# Analog_Frontend_OpAmp.net
KiCad netlist of a schematic drawn in Altium Designer
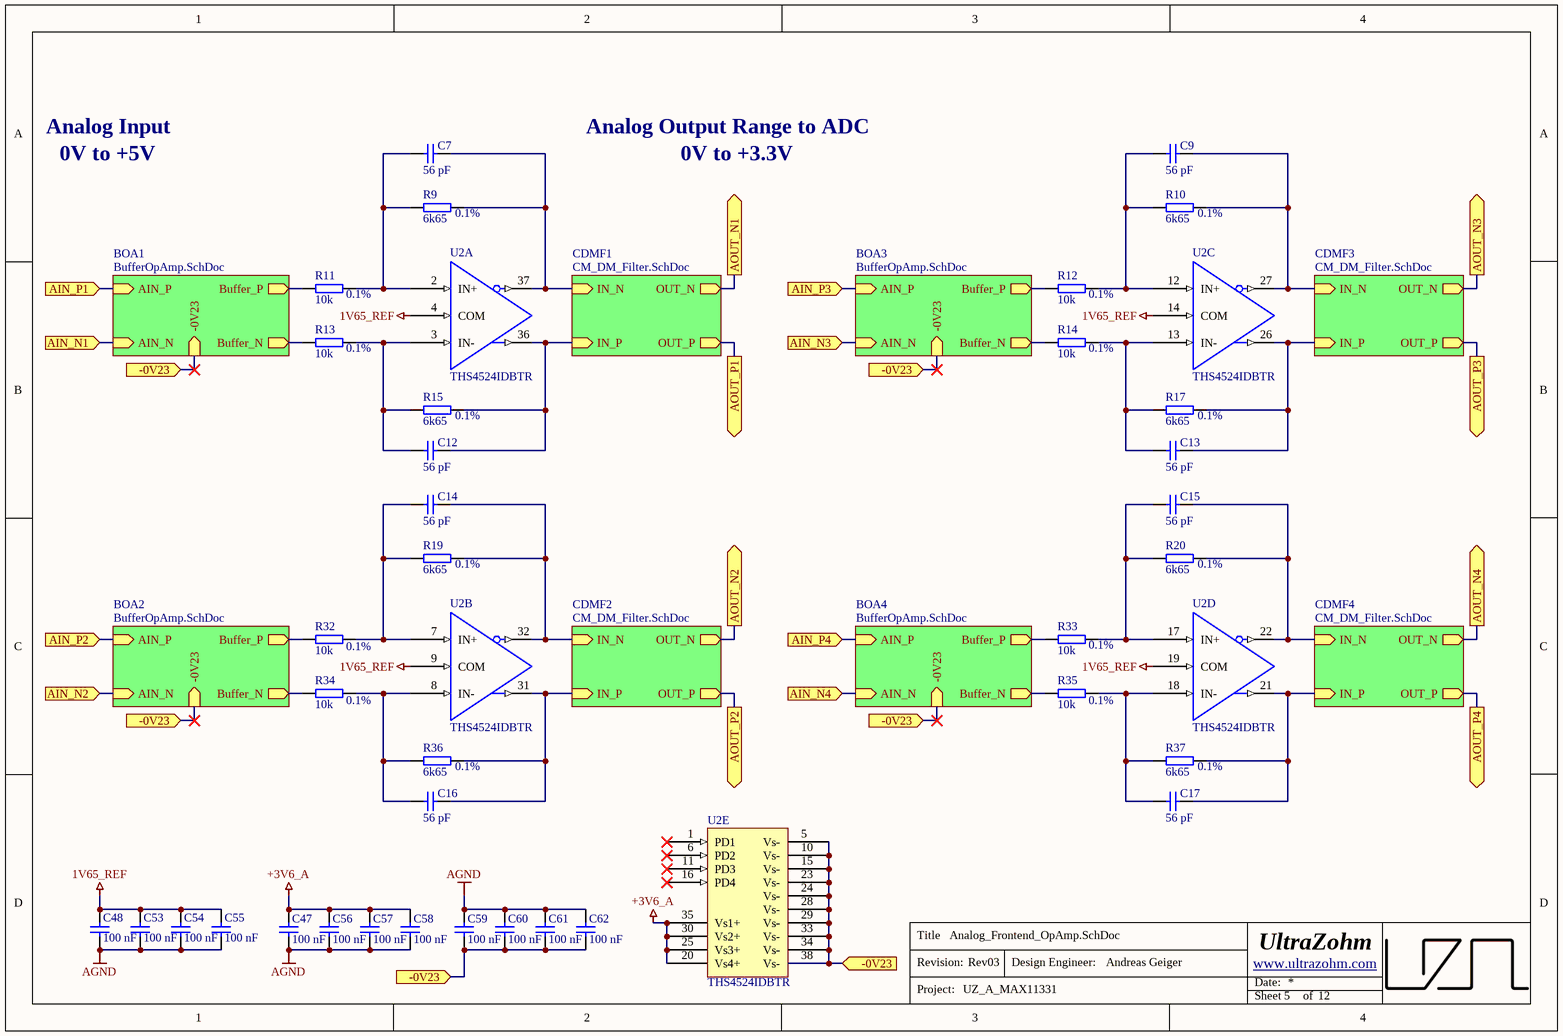
[diagram p0: Analog_Frontend_OpAmp.SchDoc]

(export (version "E")
  (design (tool "Eeschema 10.0.6"))
  (components
    (comp (ref "C7")
      (value "56 pF")
      (footprint "C_0402_TE")
      (description "Generic capacitor")
      (fields
        (field (name "MANUFACTURER PART NUMBER") "UZgen_C_0402_56pF_50V_NP0")
        (field (name "MANUFACTURER") "UZgen")
        (field (name "CREATED FROM") "UZgenTool")
      )
      (libsource (lib "user") (part "CAP-NP"))
    )
    (comp (ref "C9")
      (value "56 pF")
      (footprint "C_0402_TE")
      (description "Generic capacitor")
      (fields
        (field (name "MANUFACTURER PART NUMBER") "UZgen_C_0402_56pF_50V_NP0")
        (field (name "MANUFACTURER") "UZgen")
        (field (name "CREATED FROM") "UZgenTool")
      )
      (libsource (lib "user") (part "CAP-NP"))
    )
    (comp (ref "C12")
      (value "56 pF")
      (footprint "C_0402_TE")
      (description "Generic capacitor")
      (fields
        (field (name "MANUFACTURER PART NUMBER") "UZgen_C_0402_56pF_50V_NP0")
        (field (name "MANUFACTURER") "UZgen")
        (field (name "CREATED FROM") "UZgenTool")
      )
      (libsource (lib "user") (part "CAP-NP"))
    )
    (comp (ref "C13")
      (value "56 pF")
      (footprint "C_0402_TE")
      (description "Generic capacitor")
      (fields
        (field (name "MANUFACTURER PART NUMBER") "UZgen_C_0402_56pF_50V_NP0")
        (field (name "MANUFACTURER") "UZgen")
        (field (name "CREATED FROM") "UZgenTool")
      )
      (libsource (lib "user") (part "CAP-NP"))
    )
    (comp (ref "C14")
      (value "56 pF")
      (footprint "C_0402_TE")
      (description "Generic capacitor")
      (fields
        (field (name "MANUFACTURER PART NUMBER") "UZgen_C_0402_56pF_50V_NP0")
        (field (name "MANUFACTURER") "UZgen")
        (field (name "CREATED FROM") "UZgenTool")
      )
      (libsource (lib "user") (part "CAP-NP"))
    )
    (comp (ref "C15")
      (value "56 pF")
      (footprint "C_0402_TE")
      (description "Generic capacitor")
      (fields
        (field (name "MANUFACTURER PART NUMBER") "UZgen_C_0402_56pF_50V_NP0")
        (field (name "MANUFACTURER") "UZgen")
        (field (name "CREATED FROM") "UZgenTool")
      )
      (libsource (lib "user") (part "CAP-NP"))
    )
    (comp (ref "C16")
      (value "56 pF")
      (footprint "C_0402_TE")
      (description "Generic capacitor")
      (fields
        (field (name "MANUFACTURER PART NUMBER") "UZgen_C_0402_56pF_50V_NP0")
        (field (name "MANUFACTURER") "UZgen")
        (field (name "CREATED FROM") "UZgenTool")
      )
      (libsource (lib "user") (part "CAP-NP"))
    )
    (comp (ref "C17")
      (value "56 pF")
      (footprint "C_0402_TE")
      (description "Generic capacitor")
      (fields
        (field (name "MANUFACTURER PART NUMBER") "UZgen_C_0402_56pF_50V_NP0")
        (field (name "MANUFACTURER") "UZgen")
        (field (name "CREATED FROM") "UZgenTool")
      )
      (libsource (lib "user") (part "CAP-NP"))
    )
    (comp (ref "C47")
      (value "100 nF")
      (footprint "C_0402_TE")
      (description "Generic capacitor")
      (fields
        (field (name "MANUFACTURER PART NUMBER") "UZgen_C_0402_100nF_50V_X7R")
        (field (name "MANUFACTURER") "UZgen")
        (field (name "CREATED FROM") "UZgenTool")
      )
      (libsource (lib "user") (part "CAP-NP"))
    )
    (comp (ref "C48")
      (value "100 nF")
      (footprint "C_0402_TE")
      (description "Generic capacitor")
      (fields
        (field (name "MANUFACTURER PART NUMBER") "UZgen_C_0402_100nF_50V_X7R")
        (field (name "MANUFACTURER") "UZgen")
        (field (name "CREATED FROM") "UZgenTool")
      )
      (libsource (lib "user") (part "CAP-NP"))
    )
    (comp (ref "C53")
      (value "100 nF")
      (footprint "C_0402_TE")
      (description "Generic capacitor")
      (fields
        (field (name "MANUFACTURER PART NUMBER") "UZgen_C_0402_100nF_50V_X7R")
        (field (name "MANUFACTURER") "UZgen")
        (field (name "CREATED FROM") "UZgenTool")
      )
      (libsource (lib "user") (part "CAP-NP"))
    )
    (comp (ref "C54")
      (value "100 nF")
      (footprint "C_0402_TE")
      (description "Generic capacitor")
      (fields
        (field (name "MANUFACTURER PART NUMBER") "UZgen_C_0402_100nF_50V_X7R")
        (field (name "MANUFACTURER") "UZgen")
        (field (name "CREATED FROM") "UZgenTool")
      )
      (libsource (lib "user") (part "CAP-NP"))
    )
    (comp (ref "C55")
      (value "100 nF")
      (footprint "C_0402_TE")
      (description "Generic capacitor")
      (fields
        (field (name "MANUFACTURER PART NUMBER") "UZgen_C_0402_100nF_50V_X7R")
        (field (name "MANUFACTURER") "UZgen")
        (field (name "CREATED FROM") "UZgenTool")
      )
      (libsource (lib "user") (part "CAP-NP"))
    )
    (comp (ref "C56")
      (value "100 nF")
      (footprint "C_0402_TE")
      (description "Generic capacitor")
      (fields
        (field (name "MANUFACTURER PART NUMBER") "UZgen_C_0402_100nF_50V_X7R")
        (field (name "MANUFACTURER") "UZgen")
        (field (name "CREATED FROM") "UZgenTool")
      )
      (libsource (lib "user") (part "CAP-NP"))
    )
    (comp (ref "C57")
      (value "100 nF")
      (footprint "C_0402_TE")
      (description "Generic capacitor")
      (fields
        (field (name "MANUFACTURER PART NUMBER") "UZgen_C_0402_100nF_50V_X7R")
        (field (name "MANUFACTURER") "UZgen")
        (field (name "CREATED FROM") "UZgenTool")
      )
      (libsource (lib "user") (part "CAP-NP"))
    )
    (comp (ref "C58")
      (value "100 nF")
      (footprint "C_0402_TE")
      (description "Generic capacitor")
      (fields
        (field (name "MANUFACTURER PART NUMBER") "UZgen_C_0402_100nF_50V_X7R")
        (field (name "MANUFACTURER") "UZgen")
        (field (name "CREATED FROM") "UZgenTool")
      )
      (libsource (lib "user") (part "CAP-NP"))
    )
    (comp (ref "C59")
      (value "100 nF")
      (footprint "C_0402_TE")
      (description "Generic capacitor")
      (fields
        (field (name "MANUFACTURER PART NUMBER") "UZgen_C_0402_100nF_50V_X7R")
        (field (name "MANUFACTURER") "UZgen")
        (field (name "CREATED FROM") "UZgenTool")
      )
      (libsource (lib "user") (part "CAP-NP"))
    )
    (comp (ref "C60")
      (value "100 nF")
      (footprint "C_0402_TE")
      (description "Generic capacitor")
      (fields
        (field (name "MANUFACTURER PART NUMBER") "UZgen_C_0402_100nF_50V_X7R")
        (field (name "MANUFACTURER") "UZgen")
        (field (name "CREATED FROM") "UZgenTool")
      )
      (libsource (lib "user") (part "CAP-NP"))
    )
    (comp (ref "C61")
      (value "100 nF")
      (footprint "C_0402_TE")
      (description "Generic capacitor")
      (fields
        (field (name "MANUFACTURER PART NUMBER") "UZgen_C_0402_100nF_50V_X7R")
        (field (name "MANUFACTURER") "UZgen")
        (field (name "CREATED FROM") "UZgenTool")
      )
      (libsource (lib "user") (part "CAP-NP"))
    )
    (comp (ref "C62")
      (value "100 nF")
      (footprint "C_0402_TE")
      (description "Generic capacitor")
      (fields
        (field (name "MANUFACTURER PART NUMBER") "UZgen_C_0402_100nF_50V_X7R")
        (field (name "MANUFACTURER") "UZgen")
        (field (name "CREATED FROM") "UZgenTool")
      )
      (libsource (lib "user") (part "CAP-NP"))
    )
    (comp (ref "R9")
      (value "6k65")
      (footprint "R_0402_TE")
      (description "62.5mW Thin Film Resistor ±25ppm/℃ ±0.1% 6.65kΩ 0402 Chip Resistor - Surface Mount ROHS")
      (fields
        (field (name "MANUFACTURER PART NUMBER") "RT0402BRD076K65L")
        (field (name "MANUFACTURER") "YAGEO")
        (field (name "TOLERANCE") "0.1%")
        (field (name "CREATED FROM") "AGeiger")
      )
      (libsource (lib "user") (part "Resistor"))
    )
    (comp (ref "R10")
      (value "6k65")
      (footprint "R_0402_TE")
      (description "62.5mW Thin Film Resistor ±25ppm/℃ ±0.1% 6.65kΩ 0402 Chip Resistor - Surface Mount ROHS")
      (fields
        (field (name "MANUFACTURER PART NUMBER") "RT0402BRD076K65L")
        (field (name "MANUFACTURER") "YAGEO")
        (field (name "TOLERANCE") "0.1%")
        (field (name "CREATED FROM") "AGeiger")
      )
      (libsource (lib "user") (part "Resistor"))
    )
    (comp (ref "R11")
      (value "10k")
      (footprint "R_0402_TE")
      (description "62.5mW Thin Film Resistor 50V ±25ppm/℃ ±0.1% 10kΩ 0402 Chip Resistor - Surface Mount ROHS")
      (fields
        (field (name "MANUFACTURER PART NUMBER") "RT0402BRD0710KL")
        (field (name "MANUFACTURER") "YAGEO")
        (field (name "TOLERANCE") "0.1%")
        (field (name "CREATED FROM") "AGeiger")
      )
      (libsource (lib "user") (part "Resistor"))
    )
    (comp (ref "R12")
      (value "10k")
      (footprint "R_0402_TE")
      (description "62.5mW Thin Film Resistor 50V ±25ppm/℃ ±0.1% 10kΩ 0402 Chip Resistor - Surface Mount ROHS")
      (fields
        (field (name "MANUFACTURER PART NUMBER") "RT0402BRD0710KL")
        (field (name "MANUFACTURER") "YAGEO")
        (field (name "TOLERANCE") "0.1%")
        (field (name "CREATED FROM") "AGeiger")
      )
      (libsource (lib "user") (part "Resistor"))
    )
    (comp (ref "R13")
      (value "10k")
      (footprint "R_0402_TE")
      (description "62.5mW Thin Film Resistor 50V ±25ppm/℃ ±0.1% 10kΩ 0402 Chip Resistor - Surface Mount ROHS")
      (fields
        (field (name "MANUFACTURER PART NUMBER") "RT0402BRD0710KL")
        (field (name "MANUFACTURER") "YAGEO")
        (field (name "TOLERANCE") "0.1%")
        (field (name "CREATED FROM") "AGeiger")
      )
      (libsource (lib "user") (part "Resistor"))
    )
    (comp (ref "R14")
      (value "10k")
      (footprint "R_0402_TE")
      (description "62.5mW Thin Film Resistor 50V ±25ppm/℃ ±0.1% 10kΩ 0402 Chip Resistor - Surface Mount ROHS")
      (fields
        (field (name "MANUFACTURER PART NUMBER") "RT0402BRD0710KL")
        (field (name "MANUFACTURER") "YAGEO")
        (field (name "TOLERANCE") "0.1%")
        (field (name "CREATED FROM") "AGeiger")
      )
      (libsource (lib "user") (part "Resistor"))
    )
    (comp (ref "R15")
      (value "6k65")
      (footprint "R_0402_TE")
      (description "62.5mW Thin Film Resistor ±25ppm/℃ ±0.1% 6.65kΩ 0402 Chip Resistor - Surface Mount ROHS")
      (fields
        (field (name "MANUFACTURER PART NUMBER") "RT0402BRD076K65L")
        (field (name "MANUFACTURER") "YAGEO")
        (field (name "TOLERANCE") "0.1%")
        (field (name "CREATED FROM") "AGeiger")
      )
      (libsource (lib "user") (part "Resistor"))
    )
    (comp (ref "R17")
      (value "6k65")
      (footprint "R_0402_TE")
      (description "62.5mW Thin Film Resistor ±25ppm/℃ ±0.1% 6.65kΩ 0402 Chip Resistor - Surface Mount ROHS")
      (fields
        (field (name "MANUFACTURER PART NUMBER") "RT0402BRD076K65L")
        (field (name "MANUFACTURER") "YAGEO")
        (field (name "TOLERANCE") "0.1%")
        (field (name "CREATED FROM") "AGeiger")
      )
      (libsource (lib "user") (part "Resistor"))
    )
    (comp (ref "R19")
      (value "6k65")
      (footprint "R_0402_TE")
      (description "62.5mW Thin Film Resistor ±25ppm/℃ ±0.1% 6.65kΩ 0402 Chip Resistor - Surface Mount ROHS")
      (fields
        (field (name "MANUFACTURER PART NUMBER") "RT0402BRD076K65L")
        (field (name "MANUFACTURER") "YAGEO")
        (field (name "TOLERANCE") "0.1%")
        (field (name "CREATED FROM") "AGeiger")
      )
      (libsource (lib "user") (part "Resistor"))
    )
    (comp (ref "R20")
      (value "6k65")
      (footprint "R_0402_TE")
      (description "62.5mW Thin Film Resistor ±25ppm/℃ ±0.1% 6.65kΩ 0402 Chip Resistor - Surface Mount ROHS")
      (fields
        (field (name "MANUFACTURER PART NUMBER") "RT0402BRD076K65L")
        (field (name "MANUFACTURER") "YAGEO")
        (field (name "TOLERANCE") "0.1%")
        (field (name "CREATED FROM") "AGeiger")
      )
      (libsource (lib "user") (part "Resistor"))
    )
    (comp (ref "R32")
      (value "10k")
      (footprint "R_0402_TE")
      (description "62.5mW Thin Film Resistor 50V ±25ppm/℃ ±0.1% 10kΩ 0402 Chip Resistor - Surface Mount ROHS")
      (fields
        (field (name "MANUFACTURER PART NUMBER") "RT0402BRD0710KL")
        (field (name "MANUFACTURER") "YAGEO")
        (field (name "TOLERANCE") "0.1%")
        (field (name "CREATED FROM") "AGeiger")
      )
      (libsource (lib "user") (part "Resistor"))
    )
    (comp (ref "R33")
      (value "10k")
      (footprint "R_0402_TE")
      (description "62.5mW Thin Film Resistor 50V ±25ppm/℃ ±0.1% 10kΩ 0402 Chip Resistor - Surface Mount ROHS")
      (fields
        (field (name "MANUFACTURER PART NUMBER") "RT0402BRD0710KL")
        (field (name "MANUFACTURER") "YAGEO")
        (field (name "TOLERANCE") "0.1%")
        (field (name "CREATED FROM") "AGeiger")
      )
      (libsource (lib "user") (part "Resistor"))
    )
    (comp (ref "R34")
      (value "10k")
      (footprint "R_0402_TE")
      (description "62.5mW Thin Film Resistor 50V ±25ppm/℃ ±0.1% 10kΩ 0402 Chip Resistor - Surface Mount ROHS")
      (fields
        (field (name "MANUFACTURER PART NUMBER") "RT0402BRD0710KL")
        (field (name "MANUFACTURER") "YAGEO")
        (field (name "TOLERANCE") "0.1%")
        (field (name "CREATED FROM") "AGeiger")
      )
      (libsource (lib "user") (part "Resistor"))
    )
    (comp (ref "R35")
      (value "10k")
      (footprint "R_0402_TE")
      (description "62.5mW Thin Film Resistor 50V ±25ppm/℃ ±0.1% 10kΩ 0402 Chip Resistor - Surface Mount ROHS")
      (fields
        (field (name "MANUFACTURER PART NUMBER") "RT0402BRD0710KL")
        (field (name "MANUFACTURER") "YAGEO")
        (field (name "TOLERANCE") "0.1%")
        (field (name "CREATED FROM") "AGeiger")
      )
      (libsource (lib "user") (part "Resistor"))
    )
    (comp (ref "R36")
      (value "6k65")
      (footprint "R_0402_TE")
      (description "62.5mW Thin Film Resistor ±25ppm/℃ ±0.1% 6.65kΩ 0402 Chip Resistor - Surface Mount ROHS")
      (fields
        (field (name "MANUFACTURER PART NUMBER") "RT0402BRD076K65L")
        (field (name "MANUFACTURER") "YAGEO")
        (field (name "TOLERANCE") "0.1%")
        (field (name "CREATED FROM") "AGeiger")
      )
      (libsource (lib "user") (part "Resistor"))
    )
    (comp (ref "R37")
      (value "6k65")
      (footprint "R_0402_TE")
      (description "62.5mW Thin Film Resistor ±25ppm/℃ ±0.1% 6.65kΩ 0402 Chip Resistor - Surface Mount ROHS")
      (fields
        (field (name "MANUFACTURER PART NUMBER") "RT0402BRD076K65L")
        (field (name "MANUFACTURER") "YAGEO")
        (field (name "TOLERANCE") "0.1%")
        (field (name "CREATED FROM") "AGeiger")
      )
      (libsource (lib "user") (part "Resistor"))
    )
    (comp (ref "U2")
      (value "THS4524IDBTR")
      (footprint "TSSOP-38")
      (description "Differential Amplifier, Very Low Power, Negative Rail Input")
      (fields
        (field (name "MANUFACTURER") "Texas Instruments")
        (field (name "LCSC PART NUMBER") "C2057434")
        (field (name "CREATED FROM") "MGremer")
      )
      (libsource (lib "user") (part "THS4524"))
    )
  )
  (nets
    (net (code "1") (name "+3V6_A") (class "Default")
      (node (ref "C47") (pin "1") (pinfunction "1_1") (pintype "passive"))
      (node (ref "C56") (pin "1") (pinfunction "1_1") (pintype "passive"))
      (node (ref "C57") (pin "1") (pinfunction "1_1") (pintype "passive"))
      (node (ref "C58") (pin "1") (pinfunction "1_1") (pintype "passive"))
      (node (ref "U2") (pin "20") (pinfunction "Vs4+_20") (pintype "power_in"))
      (node (ref "U2") (pin "25") (pinfunction "Vs3+_25") (pintype "power_in"))
      (node (ref "U2") (pin "30") (pinfunction "Vs2+_30") (pintype "power_in"))
      (node (ref "U2") (pin "35") (pinfunction "Vs1+_35") (pintype "power_in"))
    )
    (net (code "2") (name "/-0V23") (class "Default")
      (node (ref "C59") (pin "2") (pinfunction "2_2") (pintype "passive"))
      (node (ref "C60") (pin "2") (pinfunction "2_2") (pintype "passive"))
      (node (ref "C61") (pin "2") (pinfunction "2_2") (pintype "passive"))
      (node (ref "C62") (pin "2") (pinfunction "2_2") (pintype "passive"))
      (node (ref "U2") (pin "10") (pinfunction "Vs-_10") (pintype "power_in"))
      (node (ref "U2") (pin "15") (pinfunction "Vs-_15") (pintype "passive"))
      (node (ref "U2") (pin "23") (pinfunction "Vs-_23") (pintype "power_in"))
      (node (ref "U2") (pin "24") (pinfunction "Vs-_24") (pintype "power_in"))
      (node (ref "U2") (pin "28") (pinfunction "Vs-_28") (pintype "power_in"))
      (node (ref "U2") (pin "29") (pinfunction "Vs-_29") (pintype "power_in"))
      (node (ref "U2") (pin "33") (pinfunction "Vs-_33") (pintype "power_in"))
      (node (ref "U2") (pin "34") (pinfunction "Vs-_34") (pintype "power_in"))
      (node (ref "U2") (pin "38") (pinfunction "Vs-_38") (pintype "power_in"))
      (node (ref "U2") (pin "5") (pinfunction "Vs-_5") (pintype "power_in"))
    )
    (net (code "19") (name "/Buffer_N") (class "Default")
      (node (ref "R35") (pin "2") (pinfunction "2_2") (pintype "passive"))
    )
    (net (code "20") (name "/Buffer_N_1") (class "Default")
      (node (ref "R13") (pin "2") (pinfunction "2_2") (pintype "passive"))
    )
    (net (code "21") (name "/Buffer_N_2") (class "Default")
      (node (ref "R34") (pin "2") (pinfunction "2_2") (pintype "passive"))
    )
    (net (code "22") (name "/Buffer_N_3") (class "Default")
      (node (ref "R14") (pin "2") (pinfunction "2_2") (pintype "passive"))
    )
    (net (code "23") (name "/Buffer_P") (class "Default")
      (node (ref "R33") (pin "2") (pinfunction "2_2") (pintype "passive"))
    )
    (net (code "24") (name "/Buffer_P_1") (class "Default")
      (node (ref "R11") (pin "2") (pinfunction "2_2") (pintype "passive"))
    )
    (net (code "25") (name "/Buffer_P_2") (class "Default")
      (node (ref "R32") (pin "2") (pinfunction "2_2") (pintype "passive"))
    )
    (net (code "26") (name "/Buffer_P_3") (class "Default")
      (node (ref "R12") (pin "2") (pinfunction "2_2") (pintype "passive"))
    )
    (net (code "27") (name "/IN_N") (class "Default")
      (node (ref "C9") (pin "2") (pinfunction "2_2") (pintype "passive"))
      (node (ref "R10") (pin "1") (pinfunction "1_1") (pintype "passive"))
      (node (ref "U2") (pin "27") (pinfunction "OUT-_27") (pintype "output"))
    )
    (net (code "28") (name "/IN_N_1") (class "Default")
      (node (ref "C7") (pin "2") (pinfunction "2_2") (pintype "passive"))
      (node (ref "R9") (pin "1") (pinfunction "1_1") (pintype "passive"))
      (node (ref "U2") (pin "37") (pinfunction "OUT-_37") (pintype "output"))
    )
    (net (code "29") (name "/IN_N_2") (class "Default")
      (node (ref "C14") (pin "2") (pinfunction "2_2") (pintype "passive"))
      (node (ref "R19") (pin "1") (pinfunction "1_1") (pintype "passive"))
      (node (ref "U2") (pin "32") (pinfunction "OUT-_32") (pintype "output"))
    )
    (net (code "30") (name "/IN_N_3") (class "Default")
      (node (ref "C15") (pin "2") (pinfunction "2_2") (pintype "passive"))
      (node (ref "R20") (pin "1") (pinfunction "1_1") (pintype "passive"))
      (node (ref "U2") (pin "22") (pinfunction "OUT-_22") (pintype "output"))
    )
    (net (code "31") (name "/IN_P") (class "Default")
      (node (ref "C13") (pin "2") (pinfunction "2_2") (pintype "passive"))
      (node (ref "R17") (pin "1") (pinfunction "1_1") (pintype "passive"))
      (node (ref "U2") (pin "26") (pinfunction "OUT+_26") (pintype "output"))
    )
    (net (code "32") (name "/IN_P_1") (class "Default")
      (node (ref "C12") (pin "2") (pinfunction "2_2") (pintype "passive"))
      (node (ref "R15") (pin "1") (pinfunction "1_1") (pintype "passive"))
      (node (ref "U2") (pin "36") (pinfunction "OUT+_36") (pintype "output"))
    )
    (net (code "33") (name "/IN_P_2") (class "Default")
      (node (ref "C16") (pin "2") (pinfunction "2_2") (pintype "passive"))
      (node (ref "R36") (pin "1") (pinfunction "1_1") (pintype "passive"))
      (node (ref "U2") (pin "31") (pinfunction "OUT+_31") (pintype "output"))
    )
    (net (code "34") (name "/IN_P_3") (class "Default")
      (node (ref "C17") (pin "2") (pinfunction "2_2") (pintype "passive"))
      (node (ref "R37") (pin "1") (pinfunction "1_1") (pintype "passive"))
      (node (ref "U2") (pin "21") (pinfunction "OUT+_21") (pintype "output"))
    )
    (net (code "35") (name "1V65_REF") (class "Default")
      (node (ref "C48") (pin "1") (pinfunction "1_1") (pintype "passive"))
      (node (ref "C53") (pin "1") (pinfunction "1_1") (pintype "passive"))
      (node (ref "C54") (pin "1") (pinfunction "1_1") (pintype "passive"))
      (node (ref "C55") (pin "1") (pinfunction "1_1") (pintype "passive"))
      (node (ref "U2") (pin "14") (pinfunction "COM_14") (pintype "input"))
      (node (ref "U2") (pin "19") (pinfunction "COM_19") (pintype "input"))
      (node (ref "U2") (pin "4") (pinfunction "COM_4") (pintype "input"))
      (node (ref "U2") (pin "9") (pinfunction "COM_9") (pintype "input"))
    )
    (net (code "36") (name "AGND") (class "Default")
      (node (ref "C47") (pin "2") (pinfunction "2_2") (pintype "passive"))
      (node (ref "C48") (pin "2") (pinfunction "2_2") (pintype "passive"))
      (node (ref "C53") (pin "2") (pinfunction "2_2") (pintype "passive"))
      (node (ref "C54") (pin "2") (pinfunction "2_2") (pintype "passive"))
      (node (ref "C55") (pin "2") (pinfunction "2_2") (pintype "passive"))
      (node (ref "C56") (pin "2") (pinfunction "2_2") (pintype "passive"))
      (node (ref "C57") (pin "2") (pinfunction "2_2") (pintype "passive"))
      (node (ref "C58") (pin "2") (pinfunction "2_2") (pintype "passive"))
      (node (ref "C59") (pin "1") (pinfunction "1_1") (pintype "passive"))
      (node (ref "C60") (pin "1") (pinfunction "1_1") (pintype "passive"))
      (node (ref "C61") (pin "1") (pinfunction "1_1") (pintype "passive"))
      (node (ref "C62") (pin "1") (pinfunction "1_1") (pintype "passive"))
    )
    (net (code "37") (name "Net-(U2A-IN+)") (class "Default")
      (node (ref "C7") (pin "1") (pinfunction "1_1") (pintype "passive"))
      (node (ref "R11") (pin "1") (pinfunction "1_1") (pintype "passive"))
      (node (ref "R9") (pin "2") (pinfunction "2_2") (pintype "passive"))
      (node (ref "U2") (pin "2") (pinfunction "IN+_2") (pintype "input"))
    )
    (net (code "38") (name "Net-(U2A-IN-)") (class "Default")
      (node (ref "C12") (pin "1") (pinfunction "1_1") (pintype "passive"))
      (node (ref "R13") (pin "1") (pinfunction "1_1") (pintype "passive"))
      (node (ref "R15") (pin "2") (pinfunction "2_2") (pintype "passive"))
      (node (ref "U2") (pin "3") (pinfunction "IN-_3") (pintype "input"))
    )
    (net (code "39") (name "Net-(U2B-IN+)") (class "Default")
      (node (ref "C14") (pin "1") (pinfunction "1_1") (pintype "passive"))
      (node (ref "R19") (pin "2") (pinfunction "2_2") (pintype "passive"))
      (node (ref "R32") (pin "1") (pinfunction "1_1") (pintype "passive"))
      (node (ref "U2") (pin "7") (pinfunction "IN+_7") (pintype "input"))
    )
    (net (code "40") (name "Net-(U2B-IN-)") (class "Default")
      (node (ref "C16") (pin "1") (pinfunction "1_1") (pintype "passive"))
      (node (ref "R34") (pin "1") (pinfunction "1_1") (pintype "passive"))
      (node (ref "R36") (pin "2") (pinfunction "2_2") (pintype "passive"))
      (node (ref "U2") (pin "8") (pinfunction "IN-_8") (pintype "input"))
    )
    (net (code "41") (name "Net-(U2C-IN+)") (class "Default")
      (node (ref "C9") (pin "1") (pinfunction "1_1") (pintype "passive"))
      (node (ref "R10") (pin "2") (pinfunction "2_2") (pintype "passive"))
      (node (ref "R12") (pin "1") (pinfunction "1_1") (pintype "passive"))
      (node (ref "U2") (pin "12") (pinfunction "IN+_12") (pintype "input"))
    )
    (net (code "42") (name "Net-(U2C-IN-)") (class "Default")
      (node (ref "C13") (pin "1") (pinfunction "1_1") (pintype "passive"))
      (node (ref "R14") (pin "1") (pinfunction "1_1") (pintype "passive"))
      (node (ref "R17") (pin "2") (pinfunction "2_2") (pintype "passive"))
      (node (ref "U2") (pin "13") (pinfunction "IN-_13") (pintype "input"))
    )
    (net (code "43") (name "Net-(U2D-IN+)") (class "Default")
      (node (ref "C15") (pin "1") (pinfunction "1_1") (pintype "passive"))
      (node (ref "R20") (pin "2") (pinfunction "2_2") (pintype "passive"))
      (node (ref "R33") (pin "1") (pinfunction "1_1") (pintype "passive"))
      (node (ref "U2") (pin "17") (pinfunction "IN+_17") (pintype "input"))
    )
    (net (code "44") (name "Net-(U2D-IN-)") (class "Default")
      (node (ref "C17") (pin "1") (pinfunction "1_1") (pintype "passive"))
      (node (ref "R35") (pin "1") (pinfunction "1_1") (pintype "passive"))
      (node (ref "R37") (pin "2") (pinfunction "2_2") (pintype "passive"))
      (node (ref "U2") (pin "18") (pinfunction "IN-_18") (pintype "input"))
    )
    (net (code "45") (name "unconnected-(U2E-PD1-Pad1)") (class "Default")
      (node (ref "U2") (pin "1") (pinfunction "PD1_1") (pintype "input+no_connect"))
    )
    (net (code "46") (name "unconnected-(U2E-PD2-Pad6)") (class "Default")
      (node (ref "U2") (pin "6") (pinfunction "PD2_6") (pintype "input+no_connect"))
    )
    (net (code "47") (name "unconnected-(U2E-PD3-Pad11)") (class "Default")
      (node (ref "U2") (pin "11") (pinfunction "PD3_11") (pintype "input+no_connect"))
    )
    (net (code "48") (name "unconnected-(U2E-PD4-Pad16)") (class "Default")
      (node (ref "U2") (pin "16") (pinfunction "PD4_16") (pintype "input+no_connect"))
    )
  )
)
